# 16_Ethernet.net
KiCad netlist of a schematic drawn in Altium Designer
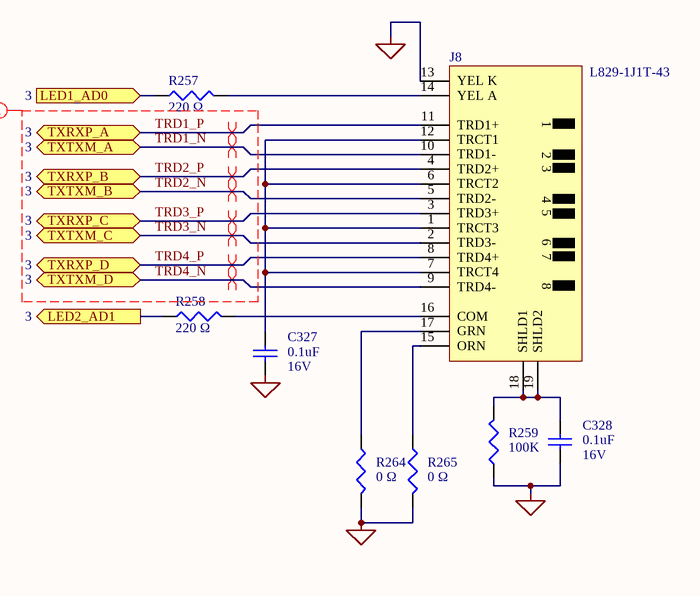
[diagram p0: 16 Ethernet.SchDoc]

(export (version "E")
  (design (tool "Eeschema 10.0.6"))
  (components
    (comp (ref "C327")
      (value "0.1uF")
      (footprint "CAP_0402")
      (description "Cap, Cer, 0.1uF, 16V, 10%, X7R, 0402")
      (fields
        (field (name "TOLERANCE") "±10%")
        (field (name "MANUFACTURER") "Murata Electronics North America")
        (field (name "VOLTAGE") "16V")
      )
      (libsource (lib "Firstview") (part "Cap 0.1uF 16V 0402"))
    )
    (comp (ref "C328")
      (value "0.1uF")
      (footprint "CAP_0402")
      (description "Cap, Cer, 0.1uF, 16V, 10%, X7R, 0402")
      (fields
        (field (name "TOLERANCE") "±10%")
        (field (name "MANUFACTURER") "Murata Electronics North America")
        (field (name "VOLTAGE") "16V")
      )
      (libsource (lib "Firstview") (part "Cap 0.1uF 16V 0402"))
    )
    (comp (ref "J8")
      (value "L829-1J1T-43")
      (footprint "CON_Ethernet_L829-1J1T-43")
      (description "Conn, Ethernet, 10/100/1000,G Base-T, TH")
      (fields (field (name "MANUFACTURER") "Bel Fuse Inc"))
      (libsource (lib "Firstview") (part "L829-1J1T-43"))
    )
    (comp (ref "R257")
      (value "220 Ω")
      (footprint "RES_0402")
      (description "Res, 220R, 0.063W, 5%, 0402")
      (fields
        (field (name "MANUFACTURER") "Stackpole Electronics Inc")
        (field (name "Comment") "Res 220R 0.063W")
      )
      (libsource (lib "Firstview") (part "Res 220R 0.063W"))
    )
    (comp (ref "R258")
      (value "220 Ω")
      (footprint "RES_0402")
      (description "Res, 220R, 0.063W, 5%, 0402")
      (fields
        (field (name "MANUFACTURER") "Stackpole Electronics Inc")
        (field (name "Comment") "Res 220R 0.063W")
      )
      (libsource (lib "Firstview") (part "Res 220R 0.063W"))
    )
    (comp (ref "R259")
      (value "100K")
      (footprint "RES_0402")
      (description "Res, 100K, 0.1W, 1%, 0402")
      (fields
        (field (name "MANUFACTURER") "Panasonic Electronic Components")
        (field (name "Comment") "Res 100K 0.1W")
      )
      (libsource (lib "Firstview") (part "Res 100K 0.1W"))
    )
    (comp (ref "R264")
      (value "0 Ω")
      (footprint "RES_0402")
      (description "Res, 0 ohm, 1/16W, 0402")
      (fields (field (name "MANUFACTURER") "Vishay Dale") (field (name "Comment") "Res 0 ohm 0.1W"))
      (libsource (lib "Firstview") (part "Res 0 ohm 0.1W"))
    )
    (comp (ref "R265")
      (value "0 Ω")
      (footprint "RES_0402")
      (description "Res, 0 ohm, 1/16W, 0402")
      (fields (field (name "MANUFACTURER") "Vishay Dale") (field (name "Comment") "Res 0 ohm 0.1W"))
      (libsource (lib "Firstview") (part "Res 0 ohm 0.1W"))
    )
  )
  (nets
    (net (code "1") (name "/LED1_AD0") (class "Default")
      (node (ref "R257") (pin "1") (pinfunction "1_1") (pintype "passive"))
    )
    (net (code "2") (name "/LED2_AD1") (class "Default")
      (node (ref "R258") (pin "1") (pinfunction "1_1") (pintype "passive"))
    )
    (net (code "3") (name "/TRD1_N") (class "Default")
      (node (ref "J8") (pin "10") (pinfunction "TRD1-_10") (pintype "passive"))
    )
    (net (code "4") (name "/TRD1_P") (class "Default")
      (node (ref "J8") (pin "11") (pinfunction "TRD1+_11") (pintype "passive"))
    )
    (net (code "5") (name "/TRD2_N") (class "Default")
      (node (ref "J8") (pin "5") (pinfunction "TRD2-_5") (pintype "passive"))
    )
    (net (code "6") (name "/TRD2_P") (class "Default")
      (node (ref "J8") (pin "4") (pinfunction "TRD2+_4") (pintype "passive"))
    )
    (net (code "7") (name "/TRD3_N") (class "Default")
      (node (ref "J8") (pin "2") (pinfunction "TRD3-_2") (pintype "passive"))
    )
    (net (code "8") (name "/TRD3_P") (class "Default")
      (node (ref "J8") (pin "3") (pinfunction "TRD3+_3") (pintype "passive"))
    )
    (net (code "9") (name "/TRD4_N") (class "Default")
      (node (ref "J8") (pin "9") (pinfunction "TRD4-_9") (pintype "passive"))
    )
    (net (code "10") (name "/TRD4_P") (class "Default")
      (node (ref "J8") (pin "8") (pinfunction "TRD4+_8") (pintype "passive"))
    )
    (net (code "11") (name "GND") (class "Default")
      (node (ref "C327") (pin "2") (pinfunction "2_2") (pintype "passive"))
      (node (ref "C328") (pin "2") (pinfunction "2_2") (pintype "passive"))
      (node (ref "J8") (pin "13") (pinfunction "YEL_K_13") (pintype "passive"))
      (node (ref "R259") (pin "1") (pinfunction "1_1") (pintype "passive"))
      (node (ref "R264") (pin "2") (pinfunction "2_2") (pintype "passive"))
      (node (ref "R265") (pin "2") (pinfunction "2_2") (pintype "passive"))
    )
    (net (code "12") (name "Net-(J8-COM)") (class "Default")
      (node (ref "J8") (pin "16") (pinfunction "COM_16") (pintype "passive"))
      (node (ref "R258") (pin "2") (pinfunction "2_2") (pintype "passive"))
    )
    (net (code "13") (name "Net-(J8-GRN)") (class "Default")
      (node (ref "J8") (pin "17") (pinfunction "GRN_17") (pintype "passive"))
      (node (ref "R264") (pin "1") (pinfunction "1_1") (pintype "passive"))
    )
    (net (code "14") (name "Net-(J8-ORN)") (class "Default")
      (node (ref "J8") (pin "15") (pinfunction "ORN_15") (pintype "passive"))
      (node (ref "R265") (pin "1") (pinfunction "1_1") (pintype "passive"))
    )
    (net (code "15") (name "Net-(J8-SHLD1)") (class "Default")
      (node (ref "C328") (pin "1") (pinfunction "1_1") (pintype "passive"))
      (node (ref "J8") (pin "18") (pinfunction "SHLD1_18") (pintype "power_in"))
      (node (ref "J8") (pin "19") (pinfunction "SHLD2_19") (pintype "power_in"))
      (node (ref "R259") (pin "2") (pinfunction "2_2") (pintype "passive"))
    )
    (net (code "16") (name "Net-(J8-TRCT1)") (class "Default")
      (node (ref "C327") (pin "1") (pinfunction "1_1") (pintype "passive"))
      (node (ref "J8") (pin "1") (pinfunction "TRCT3_1") (pintype "passive"))
      (node (ref "J8") (pin "12") (pinfunction "TRCT1_12") (pintype "passive"))
      (node (ref "J8") (pin "6") (pinfunction "TRCT2_6") (pintype "passive"))
      (node (ref "J8") (pin "7") (pinfunction "TRCT4_7") (pintype "passive"))
    )
    (net (code "17") (name "Net-(J8-YEL_A)") (class "Default")
      (node (ref "J8") (pin "14") (pinfunction "YEL_A_14") (pintype "passive"))
      (node (ref "R257") (pin "2") (pinfunction "2_2") (pintype "passive"))
    )
  )
)
